# anodeShield.net
KiCad netlist of a schematic drawn in EAGLE
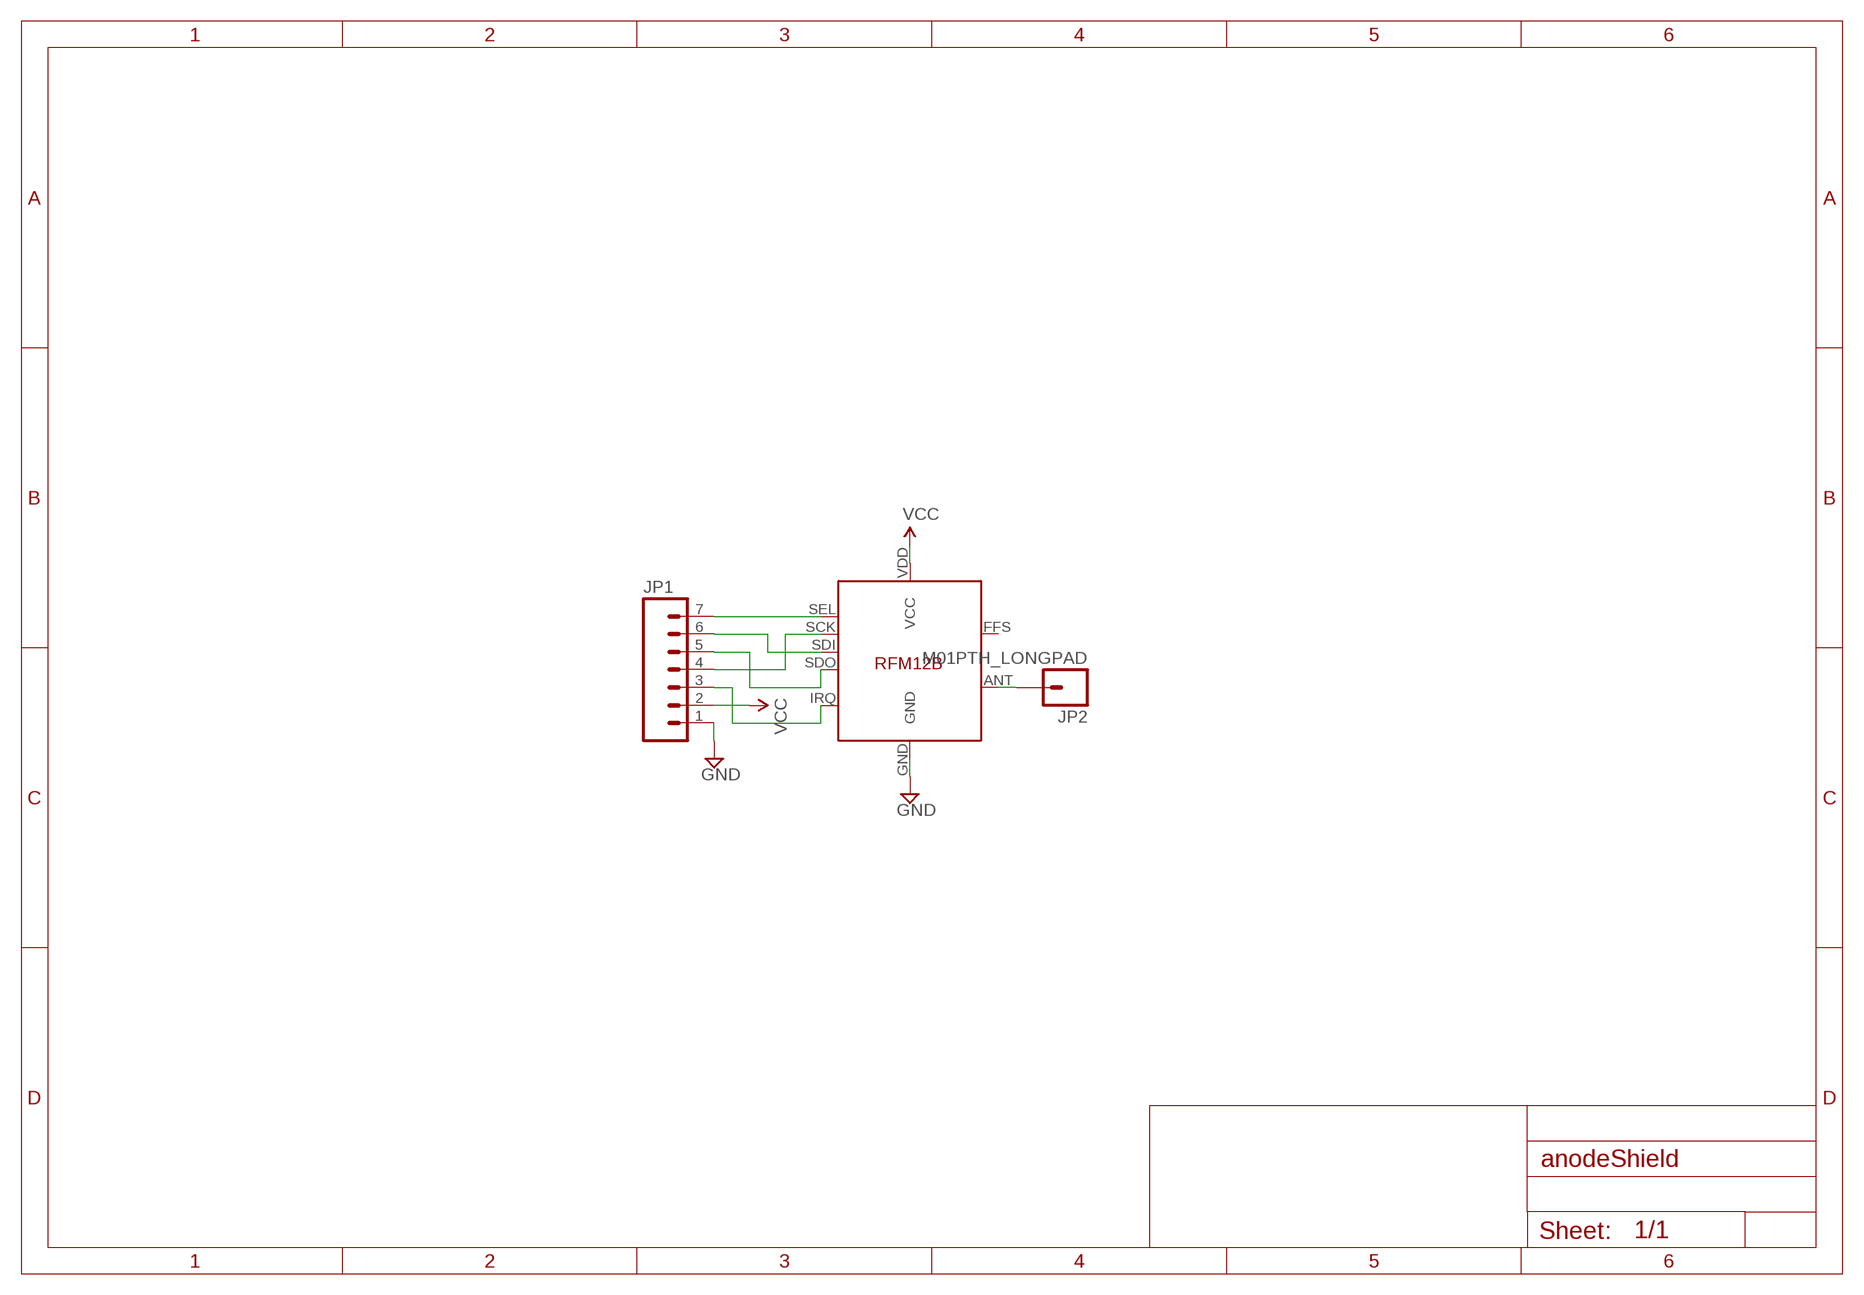
[diagram p0: schematic, sheet 1]

(export (version "E")
  (design (tool "Eeschema 10.0.6"))
  (components
    (comp (ref "JP1")
      (value "M07LONGPADS")
      (footprint "eagle-import:1X07_LONGPADS")
      (libsource (lib "eagle-import") (part "M07LONGPADS"))
    )
    (comp (ref "JP2")
      (value "M01PTH_LONGPAD")
      (footprint "eagle-import:1X01_LONGPAD")
      (libsource (lib "eagle-import") (part "M01PTH_LONGPAD"))
    )
    (comp (ref "U$1")
      (value "RFM12B")
      (footprint "eagle-import:RFM12B")
      (libsource (lib "eagle-import") (part "RFM12B"))
    )
  )
  (nets
    (net (code "1") (name "GND") (class "Default")
      (node (ref "JP1") (pin "1") (pinfunction "1_1") (pintype "passive"))
      (node (ref "U$1") (pin "GND") (pinfunction "GND_GND") (pintype "power_in"))
    )
    (net (code "2") (name "Net-(JP1-Pad3)") (class "Default")
      (node (ref "JP1") (pin "3") (pinfunction "3_3") (pintype "passive"))
      (node (ref "U$1") (pin "IRQ") (pinfunction "IRQ_IRQ") (pintype "open_collector"))
    )
    (net (code "3") (name "Net-(JP1-Pad4)") (class "Default")
      (node (ref "JP1") (pin "4") (pinfunction "4_4") (pintype "passive"))
      (node (ref "U$1") (pin "SCK") (pinfunction "SCK_SCK") (pintype "input"))
    )
    (net (code "4") (name "Net-(JP1-Pad5)") (class "Default")
      (node (ref "JP1") (pin "5") (pinfunction "5_5") (pintype "passive"))
      (node (ref "U$1") (pin "SDO") (pinfunction "SDO_SDO") (pintype "output"))
    )
    (net (code "5") (name "Net-(JP1-Pad6)") (class "Default")
      (node (ref "JP1") (pin "6") (pinfunction "6_6") (pintype "passive"))
      (node (ref "U$1") (pin "SDI") (pinfunction "SDI_SDI") (pintype "input"))
    )
    (net (code "6") (name "Net-(JP1-Pad7)") (class "Default")
      (node (ref "JP1") (pin "7") (pinfunction "7_7") (pintype "passive"))
      (node (ref "U$1") (pin "SEL") (pinfunction "SEL_SEL") (pintype "input"))
    )
    (net (code "7") (name "Net-(JP2-Pad1)") (class "Default")
      (node (ref "JP2") (pin "1") (pinfunction "1_1") (pintype "passive"))
      (node (ref "U$1") (pin "ANT") (pinfunction "ANT_ANT") (pintype "passive"))
    )
    (net (code "8") (name "VCC") (class "Default")
      (node (ref "JP1") (pin "2") (pinfunction "2_2") (pintype "passive"))
      (node (ref "U$1") (pin "VDD") (pinfunction "VCC_VDD") (pintype "power_in"))
    )
    (net (code "9") (name "unconnected-(U$1-PadFFS)") (class "Default")
      (node (ref "U$1") (pin "FFS") (pinfunction "FFS_FFS") (pintype "bidirectional"))
    )
  )
)
